# MCU_V2.net
KiCad netlist of a schematic drawn in EAGLE
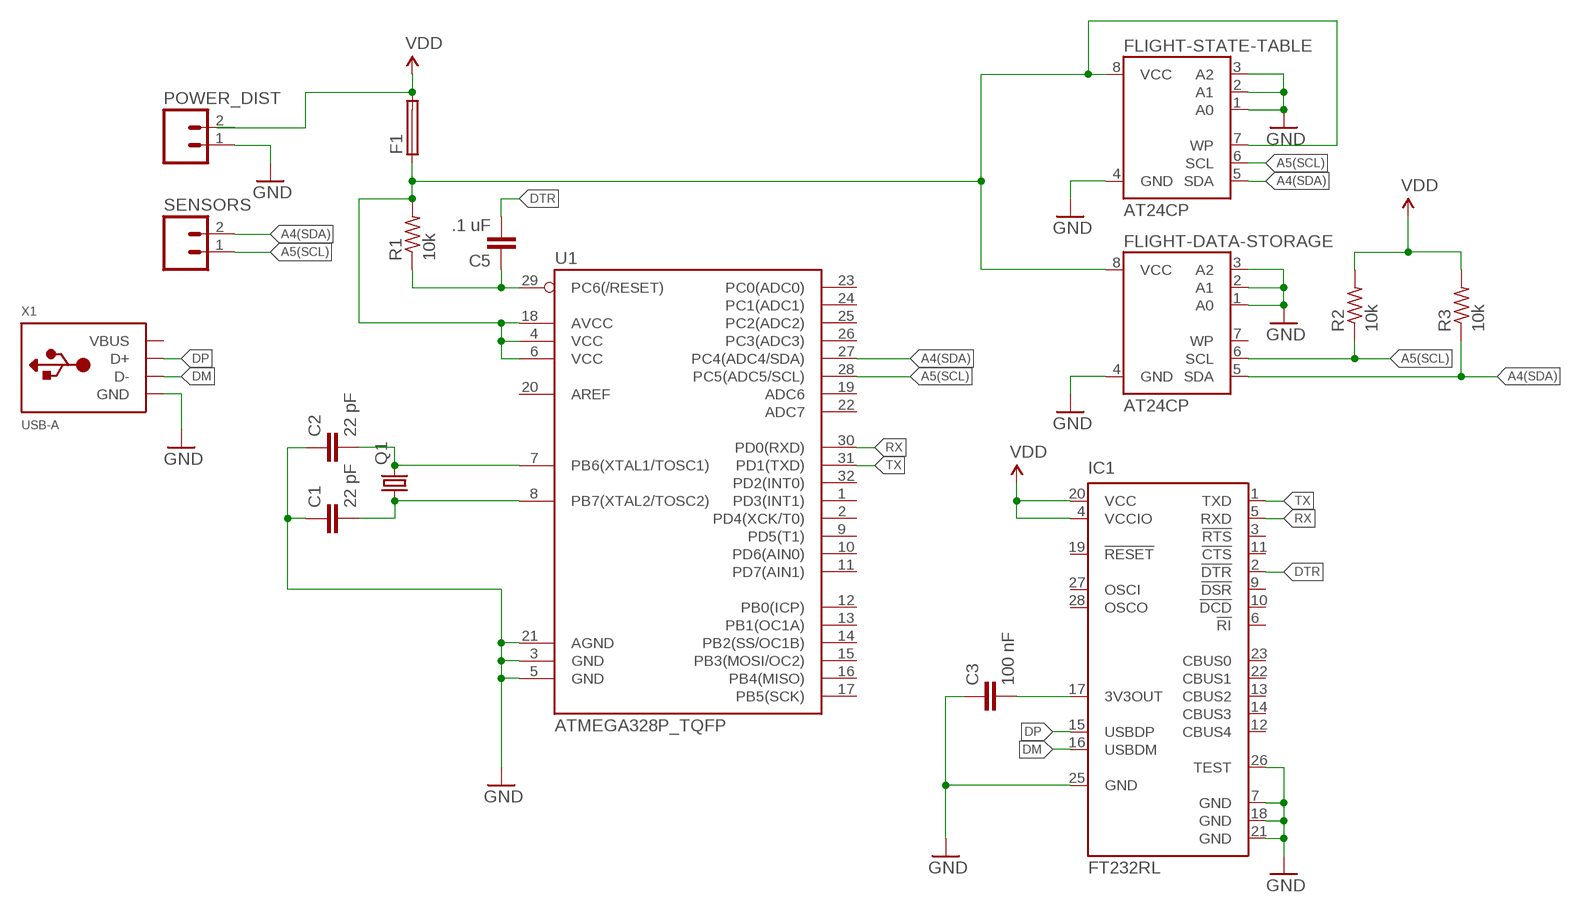
[diagram p0: schematic, sheet 1]

(export (version "E")
  (design (tool "Eeschema 10.0.6"))
  (components
    (comp (ref "C1")
      (value "22 pF")
      (footprint "eagle-import:C2.5-3")
      (libsource (lib "eagle-import") (part "C2,5-3"))
    )
    (comp (ref "C2")
      (value "22 pF")
      (footprint "eagle-import:C2.5-3")
      (libsource (lib "eagle-import") (part "C2,5-3"))
    )
    (comp (ref "C3")
      (value "100 nF")
      (footprint "eagle-import:C2.5-3")
      (libsource (lib "eagle-import") (part "C2,5-3"))
    )
    (comp (ref "C5")
      (value ".1 uF")
      (footprint "eagle-import:C2.5-3")
      (libsource (lib "eagle-import") (part "C2,5-3"))
    )
    (comp (ref "F1")
      (value "19559")
      (footprint "eagle-import:19559")
      (fields (field (name "MPN") "55900000001"))
      (libsource (lib "eagle-import") (part "19559"))
    )
    (comp (ref "FLIGHT-DATA-STORAGE")
      (value "AT24CP")
      (footprint "eagle-import:DIL08")
      (fields (field (name "MPN") "AT24C1024BW-SH-B"))
      (libsource (lib "eagle-import") (part "AT24CP"))
    )
    (comp (ref "FLIGHT-STATE-TABLE")
      (value "AT24CP")
      (footprint "eagle-import:DIL08")
      (fields (field (name "MPN") "AT24C1024BW-SH-B"))
      (libsource (lib "eagle-import") (part "AT24CP"))
    )
    (comp (ref "IC1")
      (value "FT232RL")
      (footprint "eagle-import:SSOP28")
      (libsource (lib "eagle-import") (part "FT232RL"))
    )
    (comp (ref "POWER_DIST")
      (value "M02PTH")
      (footprint "eagle-import:1X02")
      (libsource (lib "eagle-import") (part "M02PTH"))
    )
    (comp (ref "Q1")
      (value "CRYSTALHC33U-V")
      (footprint "eagle-import:HC33U-V")
      (libsource (lib "eagle-import") (part "CRYSTALHC33U-V"))
    )
    (comp (ref "R1")
      (value "10k")
      (footprint "eagle-import:R0805")
      (libsource (lib "eagle-import") (part "R-US_R0805"))
    )
    (comp (ref "R2")
      (value "10k")
      (footprint "eagle-import:R0805")
      (libsource (lib "eagle-import") (part "R-US_R0805"))
    )
    (comp (ref "R3")
      (value "10k")
      (footprint "eagle-import:R0805")
      (libsource (lib "eagle-import") (part "R-US_R0805"))
    )
    (comp (ref "SENSORS")
      (value "M02PTH")
      (footprint "eagle-import:1X02")
      (libsource (lib "eagle-import") (part "M02PTH"))
    )
    (comp (ref "U1")
      (value "ATMEGA328P_TQFP")
      (footprint "eagle-import:TQFP32-08")
      (libsource (lib "eagle-import") (part "ATMEGA328P_TQFP"))
    )
    (comp (ref "X1")
      (value "USB-A")
      (footprint "eagle-import:MOLEX_480371000")
      (libsource (lib "eagle-import") (part "USB-A"))
    )
  )
  (nets
    (net (code "1") (name "/VBUS") (class "Default")
      (node (ref "X1") (pin "1") (pinfunction "VBUS_1") (pintype "power_in"))
    )
    (net (code "2") (name "A4(SDA)") (class "Default")
      (node (ref "FLIGHT-DATA-STORAGE") (pin "5") (pinfunction "SDA_5") (pintype "bidirectional"))
      (node (ref "FLIGHT-STATE-TABLE") (pin "5") (pinfunction "SDA_5") (pintype "bidirectional"))
      (node (ref "R3") (pin "1") (pinfunction "1_1") (pintype "passive"))
      (node (ref "SENSORS") (pin "2") (pinfunction "2_2") (pintype "passive"))
      (node (ref "U1") (pin "27") (pinfunction "PC4(ADC4/SDA)_27") (pintype "bidirectional"))
    )
    (net (code "3") (name "A5(SCL)") (class "Default")
      (node (ref "FLIGHT-DATA-STORAGE") (pin "6") (pinfunction "SCL_6") (pintype "bidirectional"))
      (node (ref "FLIGHT-STATE-TABLE") (pin "6") (pinfunction "SCL_6") (pintype "bidirectional"))
      (node (ref "R2") (pin "1") (pinfunction "1_1") (pintype "passive"))
      (node (ref "SENSORS") (pin "1") (pinfunction "1_1") (pintype "passive"))
      (node (ref "U1") (pin "28") (pinfunction "PC5(ADC5/SCL)_28") (pintype "bidirectional"))
    )
    (net (code "4") (name "DM") (class "Default")
      (node (ref "IC1") (pin "16") (pinfunction "USBDM_16") (pintype "bidirectional"))
      (node (ref "X1") (pin "2") (pinfunction "D-_2") (pintype "bidirectional"))
    )
    (net (code "5") (name "DP") (class "Default")
      (node (ref "IC1") (pin "15") (pinfunction "USBDP_15") (pintype "bidirectional"))
      (node (ref "X1") (pin "3") (pinfunction "D+_3") (pintype "bidirectional"))
    )
    (net (code "6") (name "DTR") (class "Default")
      (node (ref "C5") (pin "2") (pinfunction "2_2") (pintype "passive"))
      (node (ref "IC1") (pin "2") (pinfunction "~{DTR}_2") (pintype "output"))
    )
    (net (code "7") (name "GND") (class "Default")
      (node (ref "C1") (pin "1") (pinfunction "1_1") (pintype "passive"))
      (node (ref "C2") (pin "1") (pinfunction "1_1") (pintype "passive"))
      (node (ref "C3") (pin "1") (pinfunction "1_1") (pintype "passive"))
      (node (ref "FLIGHT-DATA-STORAGE") (pin "1") (pinfunction "A0_1") (pintype "input"))
      (node (ref "FLIGHT-DATA-STORAGE") (pin "2") (pinfunction "A1_2") (pintype "input"))
      (node (ref "FLIGHT-DATA-STORAGE") (pin "3") (pinfunction "A2_3") (pintype "input"))
      (node (ref "FLIGHT-DATA-STORAGE") (pin "4") (pinfunction "GND_4") (pintype "power_in"))
      (node (ref "FLIGHT-STATE-TABLE") (pin "1") (pinfunction "A0_1") (pintype "input"))
      (node (ref "FLIGHT-STATE-TABLE") (pin "2") (pinfunction "A1_2") (pintype "input"))
      (node (ref "FLIGHT-STATE-TABLE") (pin "3") (pinfunction "A2_3") (pintype "input"))
      (node (ref "FLIGHT-STATE-TABLE") (pin "4") (pinfunction "GND_4") (pintype "power_in"))
      (node (ref "IC1") (pin "18") (pinfunction "GND_18") (pintype "power_in"))
      (node (ref "IC1") (pin "21") (pinfunction "GND_21") (pintype "power_in"))
      (node (ref "IC1") (pin "25") (pinfunction "GND_25") (pintype "power_in"))
      (node (ref "IC1") (pin "26") (pinfunction "TEST_26") (pintype "input"))
      (node (ref "IC1") (pin "7") (pinfunction "GND_7") (pintype "power_in"))
      (node (ref "POWER_DIST") (pin "1") (pinfunction "1_1") (pintype "passive"))
      (node (ref "U1") (pin "21") (pinfunction "AGND_21") (pintype "bidirectional"))
      (node (ref "U1") (pin "3") (pinfunction "GND_3") (pintype "bidirectional"))
      (node (ref "U1") (pin "5") (pinfunction "GND_5") (pintype "bidirectional"))
      (node (ref "X1") (pin "4") (pinfunction "GND_4") (pintype "power_in"))
    )
    (net (code "8") (name "Net-(FLIGHT-DATA-STORAGE-VCC)") (class "Default")
      (node (ref "F1") (pin "1") (pinfunction "1_1") (pintype "passive"))
      (node (ref "FLIGHT-DATA-STORAGE") (pin "8") (pinfunction "VCC_8") (pintype "power_in"))
      (node (ref "FLIGHT-STATE-TABLE") (pin "7") (pinfunction "WP_7") (pintype "input"))
      (node (ref "FLIGHT-STATE-TABLE") (pin "8") (pinfunction "VCC_8") (pintype "power_in"))
      (node (ref "R1") (pin "2") (pinfunction "2_2") (pintype "passive"))
      (node (ref "U1") (pin "18") (pinfunction "AVCC_18") (pintype "bidirectional"))
      (node (ref "U1") (pin "4") (pinfunction "VCC_4") (pintype "bidirectional"))
      (node (ref "U1") (pin "6") (pinfunction "VCC_6") (pintype "bidirectional"))
    )
    (net (code "9") (name "Net-(IC1-3V3OUT)") (class "Default")
      (node (ref "C3") (pin "2") (pinfunction "2_2") (pintype "passive"))
      (node (ref "IC1") (pin "17") (pinfunction "3V3OUT_17") (pintype "output"))
    )
    (net (code "10") (name "Net-(U1-PB6(XTAL1{slash}TOSC1))") (class "Default")
      (node (ref "C2") (pin "2") (pinfunction "2_2") (pintype "passive"))
      (node (ref "Q1") (pin "2") (pinfunction "2_2") (pintype "passive"))
      (node (ref "U1") (pin "7") (pinfunction "PB6(XTAL1/TOSC1)_7") (pintype "bidirectional"))
    )
    (net (code "11") (name "Net-(U1-PB7(XTAL2{slash}TOSC2))") (class "Default")
      (node (ref "C1") (pin "2") (pinfunction "2_2") (pintype "passive"))
      (node (ref "Q1") (pin "1") (pinfunction "1_1") (pintype "passive"))
      (node (ref "U1") (pin "8") (pinfunction "PB7(XTAL2/TOSC2)_8") (pintype "bidirectional"))
    )
    (net (code "12") (name "Net-(U1-PC6({slash}RESET))") (class "Default")
      (node (ref "C5") (pin "1") (pinfunction "1_1") (pintype "passive"))
      (node (ref "R1") (pin "1") (pinfunction "1_1") (pintype "passive"))
      (node (ref "U1") (pin "29") (pinfunction "PC6(/RESET)_29") (pintype "bidirectional"))
    )
    (net (code "13") (name "RX") (class "Default")
      (node (ref "IC1") (pin "5") (pinfunction "RXD_5") (pintype "input"))
      (node (ref "U1") (pin "30") (pinfunction "PD0(RXD)_30") (pintype "bidirectional"))
    )
    (net (code "14") (name "TX") (class "Default")
      (node (ref "IC1") (pin "1") (pinfunction "TXD_1") (pintype "output"))
      (node (ref "U1") (pin "31") (pinfunction "PD1(TXD)_31") (pintype "bidirectional"))
    )
    (net (code "15") (name "VDD") (class "Default")
      (node (ref "F1") (pin "2") (pinfunction "2_2") (pintype "passive"))
      (node (ref "IC1") (pin "20") (pinfunction "VCC_20") (pintype "power_in"))
      (node (ref "IC1") (pin "4") (pinfunction "VCCIO_4") (pintype "power_in"))
      (node (ref "R2") (pin "2") (pinfunction "2_2") (pintype "passive"))
      (node (ref "R3") (pin "2") (pinfunction "2_2") (pintype "passive"))
    )
    (net (code "16") (name "unconnected-(FLIGHT-DATA-STORAGE-WP-Pad7)") (class "Default")
      (node (ref "FLIGHT-DATA-STORAGE") (pin "7") (pinfunction "WP_7") (pintype "input"))
    )
    (net (code "17") (name "unconnected-(IC1-CBUS0-Pad23)") (class "Default")
      (node (ref "IC1") (pin "23") (pinfunction "CBUS0_23") (pintype "bidirectional"))
    )
    (net (code "18") (name "unconnected-(IC1-CBUS1-Pad22)") (class "Default")
      (node (ref "IC1") (pin "22") (pinfunction "CBUS1_22") (pintype "bidirectional"))
    )
    (net (code "19") (name "unconnected-(IC1-CBUS2-Pad13)") (class "Default")
      (node (ref "IC1") (pin "13") (pinfunction "CBUS2_13") (pintype "bidirectional"))
    )
    (net (code "20") (name "unconnected-(IC1-CBUS3-Pad14)") (class "Default")
      (node (ref "IC1") (pin "14") (pinfunction "CBUS3_14") (pintype "bidirectional"))
    )
    (net (code "21") (name "unconnected-(IC1-CBUS4-Pad12)") (class "Default")
      (node (ref "IC1") (pin "12") (pinfunction "CBUS4_12") (pintype "bidirectional"))
    )
    (net (code "22") (name "unconnected-(IC1-OSCI-Pad27)") (class "Default")
      (node (ref "IC1") (pin "27") (pinfunction "OSCI_27") (pintype "input"))
    )
    (net (code "23") (name "unconnected-(IC1-OSCO-Pad28)") (class "Default")
      (node (ref "IC1") (pin "28") (pinfunction "OSCO_28") (pintype "output"))
    )
    (net (code "24") (name "unconnected-(IC1-~{CTS}-Pad11)") (class "Default")
      (node (ref "IC1") (pin "11") (pinfunction "~{CTS}_11") (pintype "input"))
    )
    (net (code "25") (name "unconnected-(IC1-~{DCD}-Pad10)") (class "Default")
      (node (ref "IC1") (pin "10") (pinfunction "~{DCD}_10") (pintype "input"))
    )
    (net (code "26") (name "unconnected-(IC1-~{DSR}-Pad9)") (class "Default")
      (node (ref "IC1") (pin "9") (pinfunction "~{DSR}_9") (pintype "input"))
    )
    (net (code "27") (name "unconnected-(IC1-~{RESET}-Pad19)") (class "Default")
      (node (ref "IC1") (pin "19") (pinfunction "~{RESET}_19") (pintype "input"))
    )
    (net (code "28") (name "unconnected-(IC1-~{RI}-Pad6)") (class "Default")
      (node (ref "IC1") (pin "6") (pinfunction "~{RI}_6") (pintype "input"))
    )
    (net (code "29") (name "unconnected-(IC1-~{RTS}-Pad3)") (class "Default")
      (node (ref "IC1") (pin "3") (pinfunction "~{RTS}_3") (pintype "output"))
    )
    (net (code "30") (name "unconnected-(POWER_DIST-Pad2)") (class "Default")
      (node (ref "POWER_DIST") (pin "2") (pinfunction "2_2") (pintype "passive"))
    )
    (net (code "31") (name "unconnected-(U1-ADC6-Pad19)") (class "Default")
      (node (ref "U1") (pin "19") (pinfunction "ADC6_19") (pintype "bidirectional"))
    )
    (net (code "32") (name "unconnected-(U1-ADC7-Pad22)") (class "Default")
      (node (ref "U1") (pin "22") (pinfunction "ADC7_22") (pintype "bidirectional"))
    )
    (net (code "33") (name "unconnected-(U1-AREF-Pad20)") (class "Default")
      (node (ref "U1") (pin "20") (pinfunction "AREF_20") (pintype "bidirectional"))
    )
    (net (code "34") (name "unconnected-(U1-PB0(ICP)-Pad12)") (class "Default")
      (node (ref "U1") (pin "12") (pinfunction "PB0(ICP)_12") (pintype "bidirectional"))
    )
    (net (code "35") (name "unconnected-(U1-PB1(OC1A)-Pad13)") (class "Default")
      (node (ref "U1") (pin "13") (pinfunction "PB1(OC1A)_13") (pintype "bidirectional"))
    )
    (net (code "36") (name "unconnected-(U1-PB2(SS{slash}OC1B)-Pad14)") (class "Default")
      (node (ref "U1") (pin "14") (pinfunction "PB2(SS/OC1B)_14") (pintype "bidirectional"))
    )
    (net (code "37") (name "unconnected-(U1-PB3(MOSI{slash}OC2)-Pad15)") (class "Default")
      (node (ref "U1") (pin "15") (pinfunction "PB3(MOSI/OC2)_15") (pintype "bidirectional"))
    )
    (net (code "38") (name "unconnected-(U1-PB4(MISO)-Pad16)") (class "Default")
      (node (ref "U1") (pin "16") (pinfunction "PB4(MISO)_16") (pintype "bidirectional"))
    )
    (net (code "39") (name "unconnected-(U1-PB5(SCK)-Pad17)") (class "Default")
      (node (ref "U1") (pin "17") (pinfunction "PB5(SCK)_17") (pintype "bidirectional"))
    )
    (net (code "40") (name "unconnected-(U1-PC0(ADC0)-Pad23)") (class "Default")
      (node (ref "U1") (pin "23") (pinfunction "PC0(ADC0)_23") (pintype "bidirectional"))
    )
    (net (code "41") (name "unconnected-(U1-PC1(ADC1)-Pad24)") (class "Default")
      (node (ref "U1") (pin "24") (pinfunction "PC1(ADC1)_24") (pintype "bidirectional"))
    )
    (net (code "42") (name "unconnected-(U1-PC2(ADC2)-Pad25)") (class "Default")
      (node (ref "U1") (pin "25") (pinfunction "PC2(ADC2)_25") (pintype "bidirectional"))
    )
    (net (code "43") (name "unconnected-(U1-PC3(ADC3)-Pad26)") (class "Default")
      (node (ref "U1") (pin "26") (pinfunction "PC3(ADC3)_26") (pintype "bidirectional"))
    )
    (net (code "44") (name "unconnected-(U1-PD2(INT0)-Pad32)") (class "Default")
      (node (ref "U1") (pin "32") (pinfunction "PD2(INT0)_32") (pintype "bidirectional"))
    )
    (net (code "45") (name "unconnected-(U1-PD3(INT1)-Pad1)") (class "Default")
      (node (ref "U1") (pin "1") (pinfunction "PD3(INT1)_1") (pintype "bidirectional"))
    )
    (net (code "46") (name "unconnected-(U1-PD4(XCK{slash}T0)-Pad2)") (class "Default")
      (node (ref "U1") (pin "2") (pinfunction "PD4(XCK/T0)_2") (pintype "bidirectional"))
    )
    (net (code "47") (name "unconnected-(U1-PD5(T1)-Pad9)") (class "Default")
      (node (ref "U1") (pin "9") (pinfunction "PD5(T1)_9") (pintype "bidirectional"))
    )
    (net (code "48") (name "unconnected-(U1-PD6(AIN0)-Pad10)") (class "Default")
      (node (ref "U1") (pin "10") (pinfunction "PD6(AIN0)_10") (pintype "bidirectional"))
    )
    (net (code "49") (name "unconnected-(U1-PD7(AIN1)-Pad11)") (class "Default")
      (node (ref "U1") (pin "11") (pinfunction "PD7(AIN1)_11") (pintype "bidirectional"))
    )
  )
)
